# OMD_TOF.net
KiCad netlist of a schematic drawn in Altium Designer
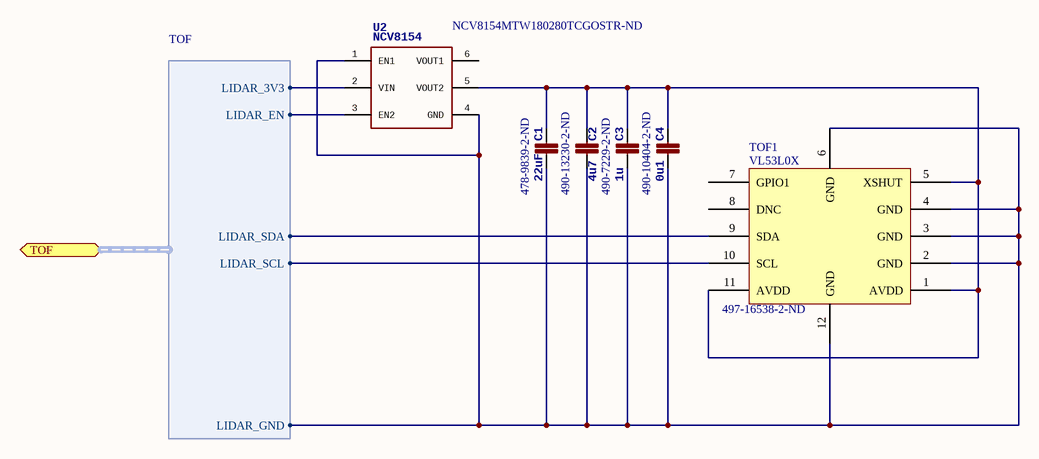
[diagram p0: OMD_TOF.SchDoc]

(export (version "E")
  (design (tool "Eeschema 10.0.6"))
  (components
    (comp (ref "C1")
      (value "22uF")
      (footprint "0201-cap")
      (description "CAP CER 22UF 6.3V X5R 0402")
      (fields (field (name "SUPPLIER PART NUMBER 1") "478-9839-2-ND"))
      (libsource (lib "OMD") (part "CAP0805"))
    )
    (comp (ref "C2")
      (value "4u7")
      (footprint "0201-cap")
      (description "CAP CER 4.7UF 6.3V X5R 0201")
      (fields (field (name "SUPPLIER PART NUMBER 1") "490-13230-2-ND"))
      (libsource (lib "OMD") (part "CAP0603"))
    )
    (comp (ref "C3")
      (value "1u")
      (footprint "0201-cap")
      (description "CAP CER 1UF 6.3V X5R 0201")
      (fields (field (name "SUPPLIER PART NUMBER 1") "490-7229-2-ND"))
      (libsource (lib "OMD") (part "CAP0603"))
    )
    (comp (ref "C4")
      (value "0u1")
      (footprint "0201-cap")
      (description "CAP CER 0.1UF 16V Y5V 0402")
      (fields (field (name "SUPPLIER PART NUMBER 1") "490-10404-2-ND"))
      (libsource (lib "OMD") (part "CAP0402"))
    )
    (comp (ref "TOF1")
      (value "VL53L0X")
      (footprint "VL53L0X")
      (fields (field (name "SUPPLIER PART NUMBER 1") "497-16538-2-ND"))
      (libsource (lib "OMD") (part "VL53L0X"))
    )
    (comp (ref "U2")
      (value "NCV8154")
      (footprint "NCV8154")
      (description "IC REG LDO 1.8v and 2.8v")
      (fields (field (name "SUPPLIER PART NUMBER 1") "NCV8154MTW180280TCGOSTR-ND"))
      (libsource (lib "OMD") (part "NCV8154"))
    )
  )
  (nets
    (net (code "2") (name "/LIDAR_3V3") (class "Default")
      (node (ref "U2") (pin "2") (pinfunction "VIN_2") (pintype "passive"))
    )
    (net (code "3") (name "/LIDAR_EN") (class "Default")
      (node (ref "U2") (pin "3") (pinfunction "EN2_3") (pintype "passive"))
    )
    (net (code "4") (name "/LIDAR_GND") (class "Default")
      (node (ref "C1") (pin "2") (pinfunction "2_2") (pintype "passive"))
      (node (ref "C2") (pin "2") (pinfunction "2_2") (pintype "passive"))
      (node (ref "C3") (pin "2") (pinfunction "2_2") (pintype "passive"))
      (node (ref "C4") (pin "2") (pinfunction "2_2") (pintype "passive"))
      (node (ref "TOF1") (pin "12") (pinfunction "GND_12") (pintype "passive"))
      (node (ref "TOF1") (pin "2") (pinfunction "GND_2") (pintype "passive"))
      (node (ref "TOF1") (pin "3") (pinfunction "GND_3") (pintype "passive"))
      (node (ref "TOF1") (pin "4") (pinfunction "GND_4") (pintype "passive"))
      (node (ref "TOF1") (pin "6") (pinfunction "GND_6") (pintype "passive"))
      (node (ref "U2") (pin "1") (pinfunction "EN1_1") (pintype "passive"))
      (node (ref "U2") (pin "4") (pinfunction "GND_4") (pintype "passive"))
    )
    (net (code "5") (name "/LIDAR_SCL") (class "Default")
      (node (ref "TOF1") (pin "10") (pinfunction "SCL_10") (pintype "passive"))
    )
    (net (code "6") (name "/LIDAR_SDA") (class "Default")
      (node (ref "TOF1") (pin "9") (pinfunction "SDA_9") (pintype "passive"))
    )
    (net (code "8") (name "Net-(TOF1-XSHUT)") (class "Default")
      (node (ref "C1") (pin "1") (pinfunction "1_1") (pintype "passive"))
      (node (ref "C2") (pin "1") (pinfunction "1_1") (pintype "passive"))
      (node (ref "C3") (pin "1") (pinfunction "1_1") (pintype "passive"))
      (node (ref "C4") (pin "1") (pinfunction "1_1") (pintype "passive"))
      (node (ref "TOF1") (pin "1") (pinfunction "AVDD_1") (pintype "passive"))
      (node (ref "TOF1") (pin "11") (pinfunction "AVDD_11") (pintype "passive"))
      (node (ref "TOF1") (pin "5") (pinfunction "XSHUT_5") (pintype "passive"))
      (node (ref "U2") (pin "5") (pinfunction "VOUT2_5") (pintype "passive"))
    )
    (net (code "9") (name "unconnected-(TOF1-DNC-Pad8)") (class "Default")
      (node (ref "TOF1") (pin "8") (pinfunction "DNC_8") (pintype "passive"))
    )
    (net (code "10") (name "unconnected-(TOF1-GPIO1-Pad7)") (class "Default")
      (node (ref "TOF1") (pin "7") (pinfunction "GPIO1_7") (pintype "passive"))
    )
    (net (code "11") (name "unconnected-(U2-VOUT1-Pad6)") (class "Default")
      (node (ref "U2") (pin "6") (pinfunction "VOUT1_6") (pintype "passive"))
    )
  )
)
